# input.net
KiCad netlist of a schematic drawn in Altium Designer
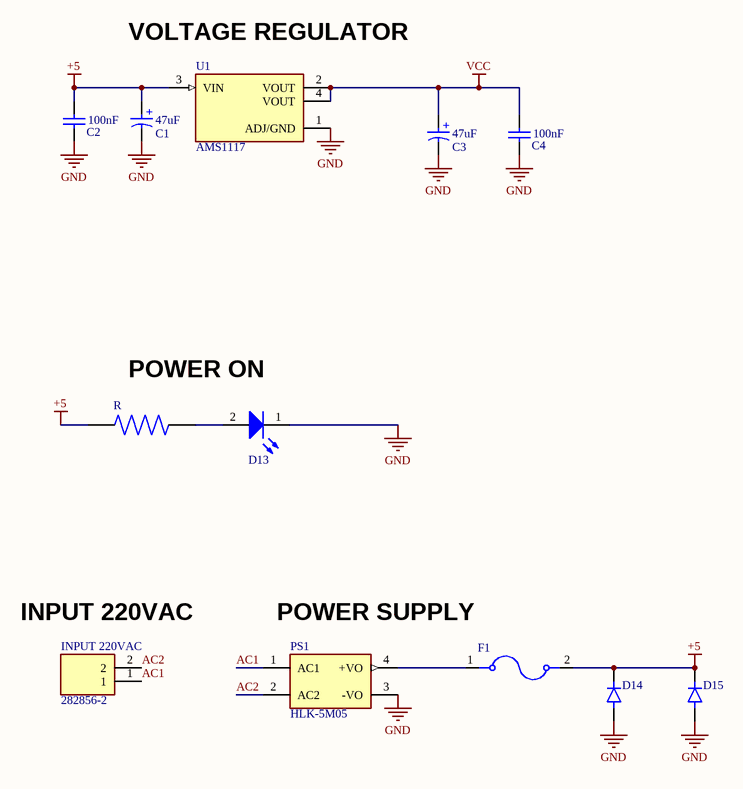
[diagram p0: input.SchDoc]

(export (version "E")
  (design (tool "Eeschema 10.0.6"))
  (components
    (comp (ref "C1")
      (value "47uF")
      (footprint "WCAP-ASLI_D6.3H7.7")
      (description "WCAP-ASLI Aluminum Electrolytic Capacitor, V-Chip, D6.3 x H5.5mm, 47uF, 25V")
      (fields
        (field (name "MANUFACTURER PART NUMBER") "865080443007")
        (field (name "MANUFACTURER") "Wurth Elektronik")
        (field (name "CAPACITANCE") "47uF")
      )
      (libsource (lib "input") (part "865080443007"))
    )
    (comp (ref "C2")
      (value "100nF")
      (footprint "WCAP-CSGP_0603_L1.6W0.8H0.8_Wave")
      (description "WCAP-CSGP Multilayer Ceramic Chip Capacitor, General Purpose, size 0603, X7R, 100nF, 25VDC")
      (fields
        (field (name "MANUFACTURER PART NUMBER") "885012206071")
        (field (name "MANUFACTURER") "Wurth Elektronik")
      )
      (libsource (lib "input") (part "885012206071"))
    )
    (comp (ref "C3")
      (value "47uF")
      (footprint "WCAP-ASLI_D6.3H7.7")
      (description "WCAP-ASLI Aluminum Electrolytic Capacitor, V-Chip, D6.3 x H5.5mm, 47uF, 25V")
      (fields
        (field (name "MANUFACTURER PART NUMBER") "865080443007")
        (field (name "MANUFACTURER") "Wurth Elektronik")
        (field (name "CAPACITANCE") "47uF")
      )
      (libsource (lib "input") (part "865080443007"))
    )
    (comp (ref "C4")
      (value "100nF")
      (footprint "WCAP-CSGP_0603_L1.6W0.8H0.8_Wave")
      (description "WCAP-CSGP Multilayer Ceramic Chip Capacitor, General Purpose, size 0603, X7R, 100nF, 25VDC")
      (fields
        (field (name "MANUFACTURER PART NUMBER") "885012206071")
        (field (name "MANUFACTURER") "Wurth Elektronik")
        (field (name "CAPACITANCE") "100nF")
      )
      (libsource (lib "input") (part "885012206071"))
    )
    (comp (ref "D13")
      (value "Infrared, 1.4V, 140°")
      (footprint "WL-SICW_0805_L2W1.3H0.8")
      (description "WL-SICW SMT Chip LED Infrared Waterclear, size 1206, Infrared, 1.4V, 140°")
      (fields
        (field (name "MANUFACTURER PART NUMBER") "15412085BA400")
        (field (name "MANUFACTURER") "Wurth Elektronik")
      )
      (libsource (lib "input") (part "15412085BA400"))
    )
    (comp (ref "D14")
      (value "S1G")
      (footprint "DIO_S1G")
      (description "Diode Standard 400 V 1A Surface Mount DO-214AC (SMA)")
      (fields (field (name "MF") "ON Semiconductor"))
      (libsource (lib "input") (part "S1G"))
    )
    (comp (ref "D15")
      (value "S1G")
      (footprint "DIO_S1G")
      (description "Diode Standard 400 V 1A Surface Mount DO-214AC (SMA)")
      (fields (field (name "MF") "ON Semiconductor"))
      (libsource (lib "input") (part "S1G"))
    )
    (comp (ref "F1")
      (value "0154004.DR")
      (footprint "input:FUSE_0154004.DR")
      (description "154/154T/154L/154TL Series OMNI-BLOKÂ® Fuse and Holder Assembly")
      (libsource (lib "input") (part "0154004.DR"))
    )
    (comp (ref "INPUT 220VAC")
      (value "282856-2")
      (footprint "TE_282856-2")
      (description "TERMI-BLOK PCB MOUNT 2P")
      (fields (field (name "MF") "TE Connectivity"))
      (libsource (lib "input") (part "282856-2"))
    )
    (comp (ref "PS1")
      (value "HLK-5M05")
      (footprint "CONV_HLK-5M05")
      (description "AC DC 220V to 5V 5W 5Watt Isolated Switching Step-Down Power Supply Module Converter")
      (fields (field (name "MF") "Hi-link"))
      (libsource (lib "input") (part "HLK-5M05"))
    )
    (comp (ref "R")
      (value "FCR1206J10R")
      (footprint "RESC3216X70N")
      (description "Res 1206 10 Ohm 5% 1/8W Â±500ppm/Â°C Molded SMD SMD T/R")
      (fields (field (name "TOLERANCE") "5%") (field (name "MF") "TE Connectivity"))
      (libsource (lib "input") (part "FCR1206J10R"))
    )
    (comp (ref "U1")
      (value "AMS1117")
      (footprint "SOT229P700X180-4N")
      (description "1A LOW DROPOUT VOLTAGE REGULATOR SOT-223")
      (fields (field (name "MF") "Advanced Monolithic Systems"))
      (libsource (lib "input") (part "AMS1117"))
    )
  )
  (nets
    (net (code "1") (name "+5") (class "Default")
      (node (ref "C1") (pin "1") (pinfunction "P_1") (pintype "passive"))
      (node (ref "C2") (pin "2") (pinfunction "2_2") (pintype "passive"))
      (node (ref "D14") (pin "1") (pinfunction "K_1") (pintype "passive"))
      (node (ref "D15") (pin "1") (pinfunction "K_1") (pintype "passive"))
      (node (ref "F1") (pin "2") (pinfunction "2_2") (pintype "passive"))
      (node (ref "R") (pin "1") (pinfunction "1_1") (pintype "passive"))
      (node (ref "U1") (pin "3") (pinfunction "VIN_3") (pintype "input"))
    )
    (net (code "2") (name "/AC1") (class "Default")
      (node (ref "INPUT 220VAC") (pin "1") (pinfunction "1_1") (pintype "passive"))
      (node (ref "PS1") (pin "1") (pinfunction "AC1_1") (pintype "power_in"))
    )
    (net (code "3") (name "/AC2") (class "Default")
      (node (ref "INPUT 220VAC") (pin "2") (pinfunction "2_2") (pintype "passive"))
      (node (ref "PS1") (pin "2") (pinfunction "AC2_2") (pintype "power_in"))
    )
    (net (code "4") (name "GND") (class "Default")
      (node (ref "C1") (pin "2") (pinfunction "N_2") (pintype "passive"))
      (node (ref "C2") (pin "1") (pinfunction "1_1") (pintype "passive"))
      (node (ref "C3") (pin "2") (pinfunction "N_2") (pintype "passive"))
      (node (ref "C4") (pin "1") (pinfunction "1_1") (pintype "passive"))
      (node (ref "D13") (pin "1") (pinfunction "K_1") (pintype "passive"))
      (node (ref "D14") (pin "2") (pinfunction "A_2") (pintype "passive"))
      (node (ref "D15") (pin "2") (pinfunction "A_2") (pintype "passive"))
      (node (ref "PS1") (pin "3") (pinfunction "-VO_3") (pintype "power_in"))
      (node (ref "U1") (pin "1") (pinfunction "ADJ/GND_1") (pintype "power_in"))
    )
    (net (code "5") (name "Net-(D13-A)") (class "Default")
      (node (ref "D13") (pin "2") (pinfunction "A_2") (pintype "passive"))
      (node (ref "R") (pin "2") (pinfunction "2_2") (pintype "passive"))
    )
    (net (code "6") (name "Net-(PS1-+VO)") (class "Default")
      (node (ref "F1") (pin "1") (pinfunction "1_1") (pintype "passive"))
      (node (ref "PS1") (pin "4") (pinfunction "+VO_4") (pintype "output"))
    )
    (net (code "7") (name "VCC") (class "Default")
      (node (ref "C3") (pin "1") (pinfunction "P_1") (pintype "passive"))
      (node (ref "C4") (pin "2") (pinfunction "2_2") (pintype "passive"))
      (node (ref "U1") (pin "2") (pinfunction "VOUT_2") (pintype "power_in"))
      (node (ref "U1") (pin "4") (pinfunction "VOUT_4") (pintype "power_in"))
    )
  )
)
